# LPCB222_-_OVERVIEW.net
KiCad netlist of a schematic drawn in Altium Designer
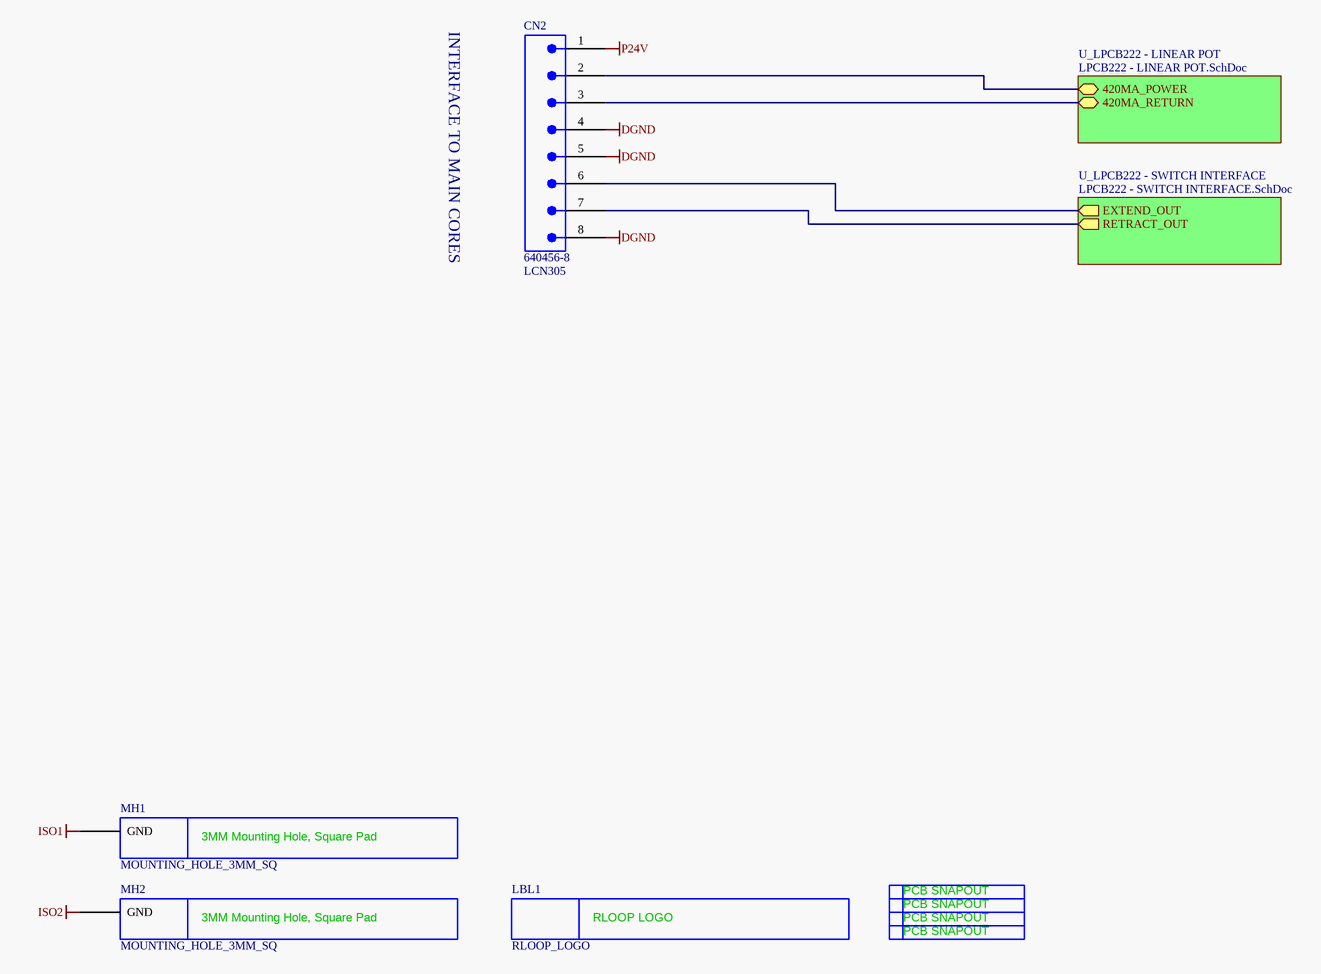
[diagram p0: LPCB222 - OVERVIEW.SchDoc]

(export (version "E")
  (design (tool "Eeschema 10.0.6"))
  (components
    (comp (ref "CN2")
      (value "640456-8")
      (footprint "640456-8")
      (description "Connector, Male Header, 8 Way")
      (fields (field (name "LDL_NUMBER") "LCN305"))
      (libsource (lib "LDL_Connectors") (part "640456-8"))
    )
    (comp (ref "LBL1")
      (value "RLOOP_LOGO")
      (footprint "RLOOP_LOGO")
      (libsource (lib "LDL_Mechanical") (part "RLOOP_LOGO"))
    )
    (comp (ref "MH1")
      (value "MOUNTING_HOLE_3MM_SQ")
      (footprint "MOUNTING_HOLE_3MM_SQ")
      (description "3MM Mouting Hole, Square")
      (libsource (lib "LDL_Mechanical") (part "MOUNTING_HOLE_3MM_SQ"))
    )
    (comp (ref "MH2")
      (value "MOUNTING_HOLE_3MM_SQ")
      (footprint "MOUNTING_HOLE_3MM_SQ")
      (description "3MM Mouting Hole, Square")
      (libsource (lib "LDL_Mechanical") (part "MOUNTING_HOLE_3MM_SQ"))
    )
    (comp (ref "SN1")
      (value "PCB_SNAPOUT")
      (footprint "SNAPOUT_NEW")
      (libsource (lib "LDL_Mechanical") (part "PCB_SNAPOUT"))
    )
    (comp (ref "SN2")
      (value "PCB_SNAPOUT")
      (footprint "SNAPOUT_NEW")
      (libsource (lib "LDL_Mechanical") (part "PCB_SNAPOUT"))
    )
    (comp (ref "SN3")
      (value "PCB_SNAPOUT")
      (footprint "SNAPOUT_NEW")
      (libsource (lib "LDL_Mechanical") (part "PCB_SNAPOUT"))
    )
    (comp (ref "SN4")
      (value "PCB_SNAPOUT")
      (footprint "SNAPOUT_NEW")
      (libsource (lib "LDL_Mechanical") (part "PCB_SNAPOUT"))
    )
  )
  (nets
    (net (code "1") (name "/420MA_POWER") (class "Default")
      (node (ref "CN2") (pin "2") (pinfunction "2_2") (pintype "passive"))
    )
    (net (code "2") (name "/420MA_RETURN") (class "Default")
      (node (ref "CN2") (pin "3") (pinfunction "3_3") (pintype "passive"))
    )
    (net (code "3") (name "/EXTEND_OUT") (class "Default")
      (node (ref "CN2") (pin "6") (pinfunction "6_6") (pintype "passive"))
    )
    (net (code "4") (name "/RETRACT_OUT") (class "Default")
      (node (ref "CN2") (pin "7") (pinfunction "7_7") (pintype "passive"))
    )
    (net (code "5") (name "DGND") (class "Default")
      (node (ref "CN2") (pin "4") (pinfunction "4_4") (pintype "passive"))
      (node (ref "CN2") (pin "5") (pinfunction "5_5") (pintype "passive"))
      (node (ref "CN2") (pin "8") (pinfunction "8_8") (pintype "passive"))
    )
    (net (code "6") (name "ISO1") (class "Default")
      (node (ref "MH1") (pin "MOUNT") (pinfunction "GND_MOUNT") (pintype "passive"))
    )
    (net (code "7") (name "ISO2") (class "Default")
      (node (ref "MH2") (pin "MOUNT") (pinfunction "GND_MOUNT") (pintype "passive"))
    )
    (net (code "8") (name "P24V") (class "Default")
      (node (ref "CN2") (pin "1") (pinfunction "1_1") (pintype "passive"))
    )
  )
)
